# 780-00057_rev2_Pg2_SCH_NRES_Crate_Slot_M.net
KiCad netlist of a schematic drawn in Altium Designer
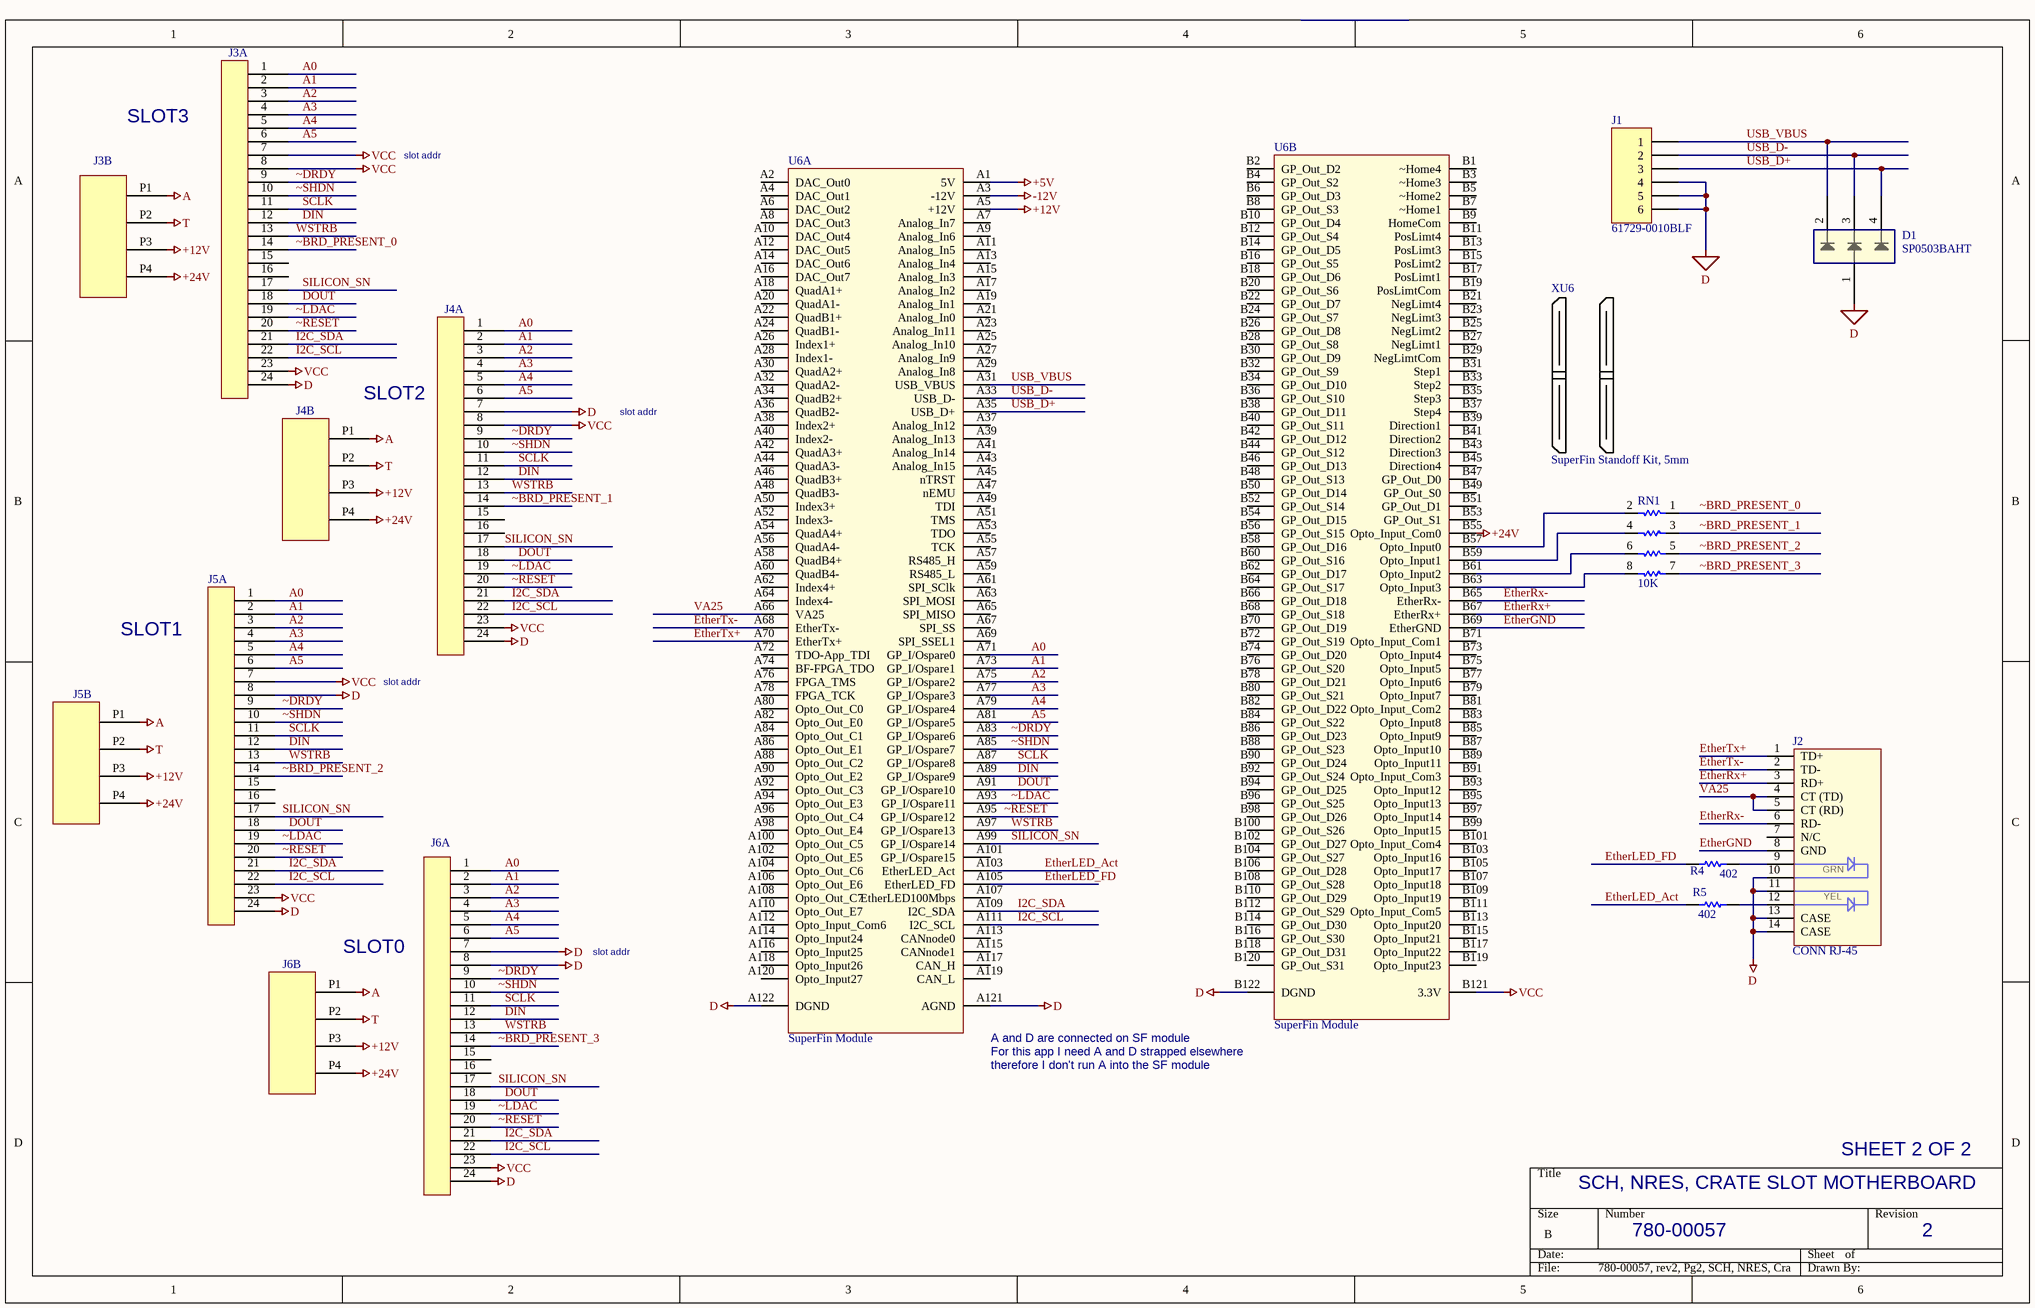
[diagram p0: 780-00057, rev2, Pg2, SCH, NRES, Crate Slot MotherBoard.SchDoc]

(export (version "E")
  (design (tool "Eeschema 10.0.6"))
  (components
    (comp (ref "D1")
      (value "SP0503BAHT")
      (footprint "SOT-143")
      (fields (field (name "MANUFACTURER") "LITTLEFUSE"))
      (libsource (lib "DJAHNG_Library_1") (part "3-Zener"))
    )
    (comp (ref "J1")
      (value "61729-0010BLF")
      (footprint "USB Vertical PCB")
      (description "Header, 6-Pin")
      (fields (field (name "MANUFACTURER") "FCI"))
      (libsource (lib "Miscellaneous Connectors") (part "Header 6"))
    )
    (comp (ref "J2")
      (value "CONN RJ-45")
      (footprint "RJ-45 w/magnetics")
      (description "Right Angle, Standard Profile, RJ45-Keyed, Flange Mount PCB Jack")
      (libsource (lib "Richs Schematic Components") (part "CONN RJ-45 with Magnetics"))
    )
    (comp (ref "J3")
      (value "Molex 46114 backplane connector, 24 signal, 4 pwr")
      (footprint "MOLEX 46114 SERIES")
      (libsource (lib "Richs Schematic Components") (part "Molex 46114 backplane connector, 24 signal, 4 pwr"))
    )
    (comp (ref "J4")
      (value "Molex 46114 backplane connector, 24 signal, 4 pwr")
      (footprint "MOLEX 46114 SERIES")
      (libsource (lib "Richs Schematic Components") (part "Molex 46114 backplane connector, 24 signal, 4 pwr"))
    )
    (comp (ref "J5")
      (value "Molex 46114 backplane connector, 24 signal, 4 pwr")
      (footprint "MOLEX 46114 SERIES")
      (libsource (lib "Richs Schematic Components") (part "Molex 46114 backplane connector, 24 signal, 4 pwr"))
    )
    (comp (ref "J6")
      (value "Molex 46114 backplane connector, 24 signal, 4 pwr")
      (footprint "MOLEX 46114 SERIES")
      (libsource (lib "Richs Schematic Components") (part "Molex 46114 backplane connector, 24 signal, 4 pwr"))
    )
    (comp (ref "R4")
      (value "402")
      (footprint "SMD_0805")
      (description "Resistor 0805")
      (fields (field (name "MANUFACTURER") "Vishay/Dale") (field (name "Comment") "Res 0805"))
      (libsource (lib "Richs Schematic Components") (part "Res SMD"))
    )
    (comp (ref "R5")
      (value "402")
      (footprint "SMD_0805")
      (description "Resistor 0805")
      (fields (field (name "MANUFACTURER") "Vishay/Dale") (field (name "Comment") "Res 0805"))
      (libsource (lib "Richs Schematic Components") (part "Res SMD"))
    )
    (comp (ref "RN1")
      (value "10K")
      (footprint "RES ARRAY 0603 x 4")
      (description "Resistor Array 4 Isolated")
      (fields (field (name "MANUFACTURER") "PANASONIC - ECG") (field (name "Comment") "RES ARRAY  x4 10K"))
      (libsource (lib "Richs Schematic Components") (part "RES ARRAY  x4 10K"))
    )
    (comp (ref "U6")
      (value "SuperFin Module")
      (footprint "SuperFin Footprint")
      (libsource (lib "Richs Schematic Components") (part "SuperFin Module"))
    )
    (comp (ref "XU6")
      (value "SuperFin Standoff Kit, 5mm")
      (libsource (lib "Richs Schematic Components") (part "SuperFin Standoff Kit, 5mm"))
    )
  )
  (nets
    (net (code "1") (name "+5V") (class "Default")
      (node (ref "U6") (pin "A1") (pinfunction "5V_A1") (pintype "passive"))
    )
    (net (code "2") (name "+12V") (class "Default")
      (node (ref "J3") (pin "P3") (pinfunction "S27_P3") (pintype "passive"))
      (node (ref "J4") (pin "P3") (pinfunction "S27_P3") (pintype "passive"))
      (node (ref "J5") (pin "P3") (pinfunction "S27_P3") (pintype "passive"))
      (node (ref "J6") (pin "P3") (pinfunction "S27_P3") (pintype "passive"))
      (node (ref "U6") (pin "A5") (pinfunction "+12V_A5") (pintype "passive"))
    )
    (net (code "3") (name "+24V") (class "Default")
      (node (ref "J3") (pin "P4") (pinfunction "S28_P4") (pintype "passive"))
      (node (ref "J4") (pin "P4") (pinfunction "S28_P4") (pintype "passive"))
      (node (ref "J5") (pin "P4") (pinfunction "S28_P4") (pintype "passive"))
      (node (ref "J6") (pin "P4") (pinfunction "S28_P4") (pintype "passive"))
      (node (ref "U6") (pin "B55") (pinfunction "Opto_Input_Com0_B55") (pintype "passive"))
    )
    (net (code "4") (name "-12V") (class "Default")
      (node (ref "U6") (pin "A3") (pinfunction "-12V_A3") (pintype "passive"))
    )
    (net (code "5") (name "/A0") (class "Default")
      (node (ref "J3") (pin "1") (pintype "passive"))
      (node (ref "J4") (pin "1") (pintype "passive"))
      (node (ref "J5") (pin "1") (pintype "passive"))
      (node (ref "J6") (pin "1") (pintype "passive"))
      (node (ref "U6") (pin "A71") (pinfunction "GP_I/Ospare0_A71") (pintype "passive"))
    )
    (net (code "6") (name "/A1") (class "Default")
      (node (ref "J3") (pin "2") (pintype "passive"))
      (node (ref "J4") (pin "2") (pintype "passive"))
      (node (ref "J5") (pin "2") (pintype "passive"))
      (node (ref "J6") (pin "2") (pintype "passive"))
      (node (ref "U6") (pin "A73") (pinfunction "GP_I/Ospare1_A73") (pintype "passive"))
    )
    (net (code "7") (name "/A2") (class "Default")
      (node (ref "J3") (pin "3") (pintype "passive"))
      (node (ref "J4") (pin "3") (pintype "passive"))
      (node (ref "J5") (pin "3") (pintype "passive"))
      (node (ref "J6") (pin "3") (pintype "passive"))
      (node (ref "U6") (pin "A75") (pinfunction "GP_I/Ospare2_A75") (pintype "passive"))
    )
    (net (code "8") (name "/A3") (class "Default")
      (node (ref "J3") (pin "4") (pintype "passive"))
      (node (ref "J4") (pin "4") (pintype "passive"))
      (node (ref "J5") (pin "4") (pintype "passive"))
      (node (ref "J6") (pin "4") (pintype "passive"))
      (node (ref "U6") (pin "A77") (pinfunction "GP_I/Ospare3_A77") (pintype "passive"))
    )
    (net (code "9") (name "/A4") (class "Default")
      (node (ref "J3") (pin "5") (pintype "passive"))
      (node (ref "J4") (pin "5") (pintype "passive"))
      (node (ref "J5") (pin "5") (pintype "passive"))
      (node (ref "J6") (pin "5") (pintype "passive"))
      (node (ref "U6") (pin "A79") (pinfunction "GP_I/Ospare4_A79") (pintype "passive"))
    )
    (net (code "10") (name "/A5") (class "Default")
      (node (ref "J3") (pin "6") (pintype "passive"))
      (node (ref "J4") (pin "6") (pintype "passive"))
      (node (ref "J5") (pin "6") (pintype "passive"))
      (node (ref "J6") (pin "6") (pintype "passive"))
      (node (ref "U6") (pin "A81") (pinfunction "GP_I/Ospare5_A81") (pintype "passive"))
    )
    (net (code "11") (name "/DIN") (class "Default")
      (node (ref "J3") (pin "12") (pintype "passive"))
      (node (ref "J4") (pin "12") (pintype "passive"))
      (node (ref "J5") (pin "12") (pintype "passive"))
      (node (ref "J6") (pin "12") (pintype "passive"))
      (node (ref "U6") (pin "A89") (pinfunction "GP_I/Ospare9_A89") (pintype "passive"))
    )
    (net (code "12") (name "/DOUT") (class "Default")
      (node (ref "J3") (pin "18") (pintype "passive"))
      (node (ref "J4") (pin "18") (pintype "passive"))
      (node (ref "J5") (pin "18") (pintype "passive"))
      (node (ref "J6") (pin "18") (pintype "passive"))
      (node (ref "U6") (pin "A91") (pinfunction "GP_I/Ospare10_A91") (pintype "passive"))
    )
    (net (code "13") (name "/EtherGND") (class "Default")
      (node (ref "J2") (pin "8") (pinfunction "GND_8") (pintype "passive"))
      (node (ref "U6") (pin "B69") (pinfunction "EtherGND_B69") (pintype "passive"))
    )
    (net (code "14") (name "/EtherLED_Act") (class "Default")
      (node (ref "R5") (pin "1") (pinfunction "1_1") (pintype "passive"))
      (node (ref "U6") (pin "A103") (pinfunction "EtherLED_Act_A103") (pintype "passive"))
    )
    (net (code "15") (name "/EtherLED_FD") (class "Default")
      (node (ref "R4") (pin "1") (pinfunction "1_1") (pintype "passive"))
      (node (ref "U6") (pin "A105") (pinfunction "EtherLED_FD_A105") (pintype "passive"))
    )
    (net (code "16") (name "/EtherRx+") (class "Default")
      (node (ref "J2") (pin "3") (pinfunction "RD+_3") (pintype "passive"))
      (node (ref "U6") (pin "B67") (pinfunction "EtherRx+_B67") (pintype "passive"))
    )
    (net (code "17") (name "/EtherRx-") (class "Default")
      (node (ref "J2") (pin "6") (pinfunction "RD-_6") (pintype "passive"))
      (node (ref "U6") (pin "B65") (pinfunction "EtherRx-_B65") (pintype "passive"))
    )
    (net (code "18") (name "/EtherTx+") (class "Default")
      (node (ref "J2") (pin "1") (pinfunction "TD+_1") (pintype "passive"))
      (node (ref "U6") (pin "A70") (pinfunction "EtherTx+_A70") (pintype "passive"))
    )
    (net (code "19") (name "/EtherTx-") (class "Default")
      (node (ref "J2") (pin "2") (pinfunction "TD-_2") (pintype "passive"))
      (node (ref "U6") (pin "A68") (pinfunction "EtherTx-_A68") (pintype "passive"))
    )
    (net (code "20") (name "/I2C_SCL") (class "Default")
      (node (ref "J3") (pin "22") (pintype "passive"))
      (node (ref "J4") (pin "22") (pintype "passive"))
      (node (ref "J5") (pin "22") (pintype "passive"))
      (node (ref "J6") (pin "22") (pintype "passive"))
      (node (ref "U6") (pin "A111") (pinfunction "I2C_SCL_A111") (pintype "passive"))
    )
    (net (code "21") (name "/I2C_SDA") (class "Default")
      (node (ref "J3") (pin "21") (pintype "passive"))
      (node (ref "J4") (pin "21") (pintype "passive"))
      (node (ref "J5") (pin "21") (pintype "passive"))
      (node (ref "J6") (pin "21") (pintype "passive"))
      (node (ref "U6") (pin "A109") (pinfunction "I2C_SDA_A109") (pintype "passive"))
    )
    (net (code "22") (name "/SCLK") (class "Default")
      (node (ref "J3") (pin "11") (pintype "passive"))
      (node (ref "J4") (pin "11") (pintype "passive"))
      (node (ref "J5") (pin "11") (pintype "passive"))
      (node (ref "J6") (pin "11") (pintype "passive"))
      (node (ref "U6") (pin "A87") (pinfunction "GP_I/Ospare8_A87") (pintype "passive"))
    )
    (net (code "23") (name "/SILICON_SN") (class "Default")
      (node (ref "J3") (pin "17") (pintype "passive"))
      (node (ref "J4") (pin "17") (pintype "passive"))
      (node (ref "J5") (pin "17") (pintype "passive"))
      (node (ref "J6") (pin "17") (pintype "passive"))
      (node (ref "U6") (pin "A99") (pinfunction "GP_I/Ospare14_A99") (pintype "passive"))
    )
    (net (code "24") (name "/USB_D+") (class "Default")
      (node (ref "D1") (pin "4") (pinfunction "K3_4") (pintype "passive"))
      (node (ref "J1") (pin "3") (pinfunction "3_3") (pintype "passive"))
      (node (ref "U6") (pin "A35") (pinfunction "USB_D+_A35") (pintype "passive"))
    )
    (net (code "25") (name "/USB_D-") (class "Default")
      (node (ref "D1") (pin "3") (pinfunction "K2_3") (pintype "passive"))
      (node (ref "J1") (pin "2") (pinfunction "2_2") (pintype "passive"))
      (node (ref "U6") (pin "A33") (pinfunction "USB_D-_A33") (pintype "passive"))
    )
    (net (code "26") (name "/USB_VBUS") (class "Default")
      (node (ref "D1") (pin "2") (pinfunction "K1_2") (pintype "passive"))
      (node (ref "J1") (pin "1") (pinfunction "1_1") (pintype "passive"))
      (node (ref "U6") (pin "A31") (pinfunction "USB_VBUS_A31") (pintype "passive"))
    )
    (net (code "27") (name "/VA25") (class "Default")
      (node (ref "J2") (pin "4") (pinfunction "CT_(TD)_4") (pintype "passive"))
      (node (ref "J2") (pin "5") (pinfunction "CT_(RD)_5") (pintype "passive"))
      (node (ref "U6") (pin "A66") (pinfunction "VA25_A66") (pintype "passive"))
    )
    (net (code "28") (name "/WSTRB") (class "Default")
      (node (ref "J3") (pin "13") (pintype "passive"))
      (node (ref "J4") (pin "13") (pintype "passive"))
      (node (ref "J5") (pin "13") (pintype "passive"))
      (node (ref "J6") (pin "13") (pintype "passive"))
      (node (ref "U6") (pin "A97") (pinfunction "GP_I/Ospare13_A97") (pintype "passive"))
    )
    (net (code "29") (name "/~BRD_PRESENT_0") (class "Default")
      (node (ref "J3") (pin "14") (pintype "passive"))
      (node (ref "RN1") (pin "1") (pinfunction "1_1") (pintype "passive"))
    )
    (net (code "30") (name "/~BRD_PRESENT_1") (class "Default")
      (node (ref "J4") (pin "14") (pintype "passive"))
      (node (ref "RN1") (pin "3") (pinfunction "3_3") (pintype "passive"))
    )
    (net (code "31") (name "/~BRD_PRESENT_2") (class "Default")
      (node (ref "J5") (pin "14") (pintype "passive"))
      (node (ref "RN1") (pin "5") (pinfunction "5_5") (pintype "passive"))
    )
    (net (code "32") (name "/~BRD_PRESENT_3") (class "Default")
      (node (ref "J6") (pin "14") (pintype "passive"))
      (node (ref "RN1") (pin "7") (pinfunction "1_7") (pintype "passive"))
    )
    (net (code "33") (name "/~DRDY") (class "Default")
      (node (ref "J3") (pin "9") (pintype "passive"))
      (node (ref "J4") (pin "9") (pintype "passive"))
      (node (ref "J5") (pin "9") (pintype "passive"))
      (node (ref "J6") (pin "9") (pintype "passive"))
      (node (ref "U6") (pin "A83") (pinfunction "GP_I/Ospare6_A83") (pintype "passive"))
    )
    (net (code "34") (name "/~LDAC") (class "Default")
      (node (ref "J3") (pin "19") (pintype "passive"))
      (node (ref "J4") (pin "19") (pintype "passive"))
      (node (ref "J5") (pin "19") (pintype "passive"))
      (node (ref "J6") (pin "19") (pintype "passive"))
      (node (ref "U6") (pin "A93") (pinfunction "GP_I/Ospare11_A93") (pintype "passive"))
    )
    (net (code "35") (name "/~RESET") (class "Default")
      (node (ref "J3") (pin "20") (pintype "passive"))
      (node (ref "J4") (pin "20") (pintype "passive"))
      (node (ref "J5") (pin "20") (pintype "passive"))
      (node (ref "J6") (pin "20") (pintype "passive"))
      (node (ref "U6") (pin "A95") (pinfunction "GP_I/Ospare12_A95") (pintype "passive"))
    )
    (net (code "36") (name "/~SHDN") (class "Default")
      (node (ref "J3") (pin "10") (pintype "passive"))
      (node (ref "J4") (pin "10") (pintype "passive"))
      (node (ref "J5") (pin "10") (pintype "passive"))
      (node (ref "J6") (pin "10") (pintype "passive"))
      (node (ref "U6") (pin "A85") (pinfunction "GP_I/Ospare7_A85") (pintype "passive"))
    )
    (net (code "37") (name "A") (class "Default")
      (node (ref "J3") (pin "P1") (pinfunction "S25_P1") (pintype "passive"))
      (node (ref "J4") (pin "P1") (pinfunction "S25_P1") (pintype "passive"))
      (node (ref "J5") (pin "P1") (pinfunction "S25_P1") (pintype "passive"))
      (node (ref "J6") (pin "P1") (pinfunction "S25_P1") (pintype "passive"))
    )
    (net (code "38") (name "D") (class "Default")
      (node (ref "D1") (pin "1") (pinfunction "A_1") (pintype "passive"))
      (node (ref "J1") (pin "4") (pinfunction "4_4") (pintype "passive"))
      (node (ref "J1") (pin "5") (pinfunction "5_5") (pintype "passive"))
      (node (ref "J1") (pin "6") (pinfunction "6_6") (pintype "passive"))
      (node (ref "J2") (pin "10") (pinfunction "GRN-Cathode_10") (pintype "passive"))
      (node (ref "J2") (pin "11") (pinfunction "YEL-Cathode_11") (pintype "passive"))
      (node (ref "J2") (pin "13") (pinfunction "CASE_13") (pintype "passive"))
      (node (ref "J2") (pin "14") (pinfunction "CASE_14") (pintype "passive"))
      (node (ref "J3") (pin "24") (pintype "passive"))
      (node (ref "J4") (pin "24") (pintype "passive"))
      (node (ref "J4") (pin "7") (pintype "passive"))
      (node (ref "J5") (pin "24") (pintype "passive"))
      (node (ref "J5") (pin "8") (pintype "passive"))
      (node (ref "J6") (pin "24") (pintype "passive"))
      (node (ref "J6") (pin "7") (pintype "passive"))
      (node (ref "J6") (pin "8") (pintype "passive"))
      (node (ref "U6") (pin "A121") (pinfunction "AGND_A121") (pintype "passive"))
      (node (ref "U6") (pin "A122") (pinfunction "DGND_A122") (pintype "passive"))
      (node (ref "U6") (pin "B122") (pinfunction "DGND_B122") (pintype "passive"))
    )
    (net (code "39") (name "Net-(J2-GRN-Anode)") (class "Default")
      (node (ref "J2") (pin "9") (pinfunction "GRN-Anode_9") (pintype "passive"))
      (node (ref "R4") (pin "2") (pinfunction "2_2") (pintype "passive"))
    )
    (net (code "40") (name "Net-(J2-YEL-Anode)") (class "Default")
      (node (ref "J2") (pin "12") (pinfunction "YEL-Anode_12") (pintype "passive"))
      (node (ref "R5") (pin "2") (pinfunction "2_2") (pintype "passive"))
    )
    (net (code "41") (name "Net-(U6B-Opto_Input0)") (class "Default")
      (node (ref "RN1") (pin "2") (pinfunction "2_2") (pintype "passive"))
      (node (ref "U6") (pin "B57") (pinfunction "Opto_Input0_B57") (pintype "passive"))
    )
    (net (code "42") (name "Net-(U6B-Opto_Input1)") (class "Default")
      (node (ref "RN1") (pin "4") (pinfunction "4_4") (pintype "passive"))
      (node (ref "U6") (pin "B59") (pinfunction "Opto_Input1_B59") (pintype "passive"))
    )
    (net (code "43") (name "Net-(U6B-Opto_Input2)") (class "Default")
      (node (ref "RN1") (pin "6") (pinfunction "6_6") (pintype "passive"))
      (node (ref "U6") (pin "B61") (pinfunction "Opto_Input2_B61") (pintype "passive"))
    )
    (net (code "44") (name "Net-(U6B-Opto_Input3)") (class "Default")
      (node (ref "RN1") (pin "8") (pinfunction "8_8") (pintype "passive"))
      (node (ref "U6") (pin "B63") (pinfunction "Opto_Input3_B63") (pintype "passive"))
    )
    (net (code "45") (name "T") (class "Default")
      (node (ref "J3") (pin "P2") (pinfunction "S26_P2") (pintype "passive"))
      (node (ref "J4") (pin "P2") (pinfunction "S26_P2") (pintype "passive"))
      (node (ref "J5") (pin "P2") (pinfunction "S26_P2") (pintype "passive"))
      (node (ref "J6") (pin "P2") (pinfunction "S26_P2") (pintype "passive"))
    )
    (net (code "46") (name "VCC") (class "Default")
      (node (ref "J3") (pin "23") (pintype "passive"))
      (node (ref "J3") (pin "7") (pintype "passive"))
      (node (ref "J3") (pin "8") (pintype "passive"))
      (node (ref "J4") (pin "23") (pintype "passive"))
      (node (ref "J4") (pin "8") (pintype "passive"))
      (node (ref "J5") (pin "23") (pintype "passive"))
      (node (ref "J5") (pin "7") (pintype "passive"))
      (node (ref "J6") (pin "23") (pintype "passive"))
      (node (ref "U6") (pin "B121") (pinfunction "3.3V_B121") (pintype "passive"))
    )
    (net (code "47") (name "unconnected-(J2-N{slash}C-Pad7)") (class "Default")
      (node (ref "J2") (pin "7") (pinfunction "N/C_7") (pintype "passive"))
    )
    (net (code "48") (name "unconnected-(J3-Pad15)") (class "Default")
      (node (ref "J3") (pin "15") (pintype "passive"))
    )
    (net (code "49") (name "unconnected-(J3-Pad16)") (class "Default")
      (node (ref "J3") (pin "16") (pintype "passive"))
    )
    (net (code "50") (name "unconnected-(J4-Pad15)") (class "Default")
      (node (ref "J4") (pin "15") (pintype "passive"))
    )
    (net (code "51") (name "unconnected-(J4-Pad16)") (class "Default")
      (node (ref "J4") (pin "16") (pintype "passive"))
    )
    (net (code "52") (name "unconnected-(J5-Pad15)") (class "Default")
      (node (ref "J5") (pin "15") (pintype "passive"))
    )
    (net (code "53") (name "unconnected-(J5-Pad16)") (class "Default")
      (node (ref "J5") (pin "16") (pintype "passive"))
    )
    (net (code "54") (name "unconnected-(J6-Pad15)") (class "Default")
      (node (ref "J6") (pin "15") (pintype "passive"))
    )
    (net (code "55") (name "unconnected-(J6-Pad16)") (class "Default")
      (node (ref "J6") (pin "16") (pintype "passive"))
    )
    (net (code "56") (name "unconnected-(U6A-Analog_In0-PadA21)") (class "Default")
      (node (ref "U6") (pin "A21") (pinfunction "Analog_In0_A21") (pintype "passive"))
    )
    (net (code "57") (name "unconnected-(U6A-Analog_In1-PadA19)") (class "Default")
      (node (ref "U6") (pin "A19") (pinfunction "Analog_In1_A19") (pintype "passive"))
    )
    (net (code "58") (name "unconnected-(U6A-Analog_In2-PadA17)") (class "Default")
      (node (ref "U6") (pin "A17") (pinfunction "Analog_In2_A17") (pintype "passive"))
    )
    (net (code "59") (name "unconnected-(U6A-Analog_In3-PadA15)") (class "Default")
      (node (ref "U6") (pin "A15") (pinfunction "Analog_In3_A15") (pintype "passive"))
    )
    (net (code "60") (name "unconnected-(U6A-Analog_In4-PadA13)") (class "Default")
      (node (ref "U6") (pin "A13") (pinfunction "Analog_In4_A13") (pintype "passive"))
    )
    (net (code "61") (name "unconnected-(U6A-Analog_In5-PadA11)") (class "Default")
      (node (ref "U6") (pin "A11") (pinfunction "Analog_In5_A11") (pintype "passive"))
    )
    (net (code "62") (name "unconnected-(U6A-Analog_In6-PadA9)") (class "Default")
      (node (ref "U6") (pin "A9") (pinfunction "Analog_In6_A9") (pintype "passive"))
    )
    (net (code "63") (name "unconnected-(U6A-Analog_In7-PadA7)") (class "Default")
      (node (ref "U6") (pin "A7") (pinfunction "Analog_In7_A7") (pintype "passive"))
    )
    (net (code "64") (name "unconnected-(U6A-Analog_In8-PadA29)") (class "Default")
      (node (ref "U6") (pin "A29") (pinfunction "Analog_In8_A29") (pintype "passive"))
    )
    (net (code "65") (name "unconnected-(U6A-Analog_In9-PadA27)") (class "Default")
      (node (ref "U6") (pin "A27") (pinfunction "Analog_In9_A27") (pintype "passive"))
    )
    (net (code "66") (name "unconnected-(U6A-Analog_In10-PadA25)") (class "Default")
      (node (ref "U6") (pin "A25") (pinfunction "Analog_In10_A25") (pintype "passive"))
    )
    (net (code "67") (name "unconnected-(U6A-Analog_In11-PadA23)") (class "Default")
      (node (ref "U6") (pin "A23") (pinfunction "Analog_In11_A23") (pintype "passive"))
    )
    (net (code "68") (name "unconnected-(U6A-Analog_In12-PadA37)") (class "Default")
      (node (ref "U6") (pin "A37") (pinfunction "Analog_In12_A37") (pintype "passive"))
    )
    (net (code "69") (name "unconnected-(U6A-Analog_In13-PadA39)") (class "Default")
      (node (ref "U6") (pin "A39") (pinfunction "Analog_In13_A39") (pintype "passive"))
    )
    (net (code "70") (name "unconnected-(U6A-Analog_In14-PadA41)") (class "Default")
      (node (ref "U6") (pin "A41") (pinfunction "Analog_In14_A41") (pintype "passive"))
    )
    (net (code "71") (name "unconnected-(U6A-Analog_In15-PadA43)") (class "Default")
      (node (ref "U6") (pin "A43") (pinfunction "Analog_In15_A43") (pintype "passive"))
    )
    (net (code "72") (name "unconnected-(U6A-BF-FPGA_TDO-PadA74)") (class "Default")
      (node (ref "U6") (pin "A74") (pinfunction "BF-FPGA_TDO_A74") (pintype "passive"))
    )
    (net (code "73") (name "unconnected-(U6A-CAN_H-PadA117)") (class "Default")
      (node (ref "U6") (pin "A117") (pinfunction "CAN_H_A117") (pintype "passive"))
    )
    (net (code "74") (name "unconnected-(U6A-CAN_L-PadA119)") (class "Default")
      (node (ref "U6") (pin "A119") (pinfunction "CAN_L_A119") (pintype "passive"))
    )
    (net (code "75") (name "unconnected-(U6A-CANnode0-PadA113)") (class "Default")
      (node (ref "U6") (pin "A113") (pinfunction "CANnode0_A113") (pintype "passive"))
    )
    (net (code "76") (name "unconnected-(U6A-CANnode1-PadA115)") (class "Default")
      (node (ref "U6") (pin "A115") (pinfunction "CANnode1_A115") (pintype "passive"))
    )
    (net (code "77") (name "unconnected-(U6A-DAC_Out0-PadA2)") (class "Default")
      (node (ref "U6") (pin "A2") (pinfunction "DAC_Out0_A2") (pintype "passive"))
    )
    (net (code "78") (name "unconnected-(U6A-DAC_Out1-PadA4)") (class "Default")
      (node (ref "U6") (pin "A4") (pinfunction "DAC_Out1_A4") (pintype "passive"))
    )
    (net (code "79") (name "unconnected-(U6A-DAC_Out2-PadA6)") (class "Default")
      (node (ref "U6") (pin "A6") (pinfunction "DAC_Out2_A6") (pintype "passive"))
    )
    (net (code "80") (name "unconnected-(U6A-DAC_Out3-PadA8)") (class "Default")
      (node (ref "U6") (pin "A8") (pinfunction "DAC_Out3_A8") (pintype "passive"))
    )
    (net (code "81") (name "unconnected-(U6A-DAC_Out4-PadA10)") (class "Default")
      (node (ref "U6") (pin "A10") (pinfunction "DAC_Out4_A10") (pintype "passive"))
    )
    (net (code "82") (name "unconnected-(U6A-DAC_Out5-PadA12)") (class "Default")
      (node (ref "U6") (pin "A12") (pinfunction "DAC_Out5_A12") (pintype "passive"))
    )
    (net (code "83") (name "unconnected-(U6A-DAC_Out6-PadA14)") (class "Default")
      (node (ref "U6") (pin "A14") (pinfunction "DAC_Out6_A14") (pintype "passive"))
    )
    (net (code "84") (name "unconnected-(U6A-DAC_Out7-PadA16)") (class "Default")
      (node (ref "U6") (pin "A16") (pinfunction "DAC_Out7_A16") (pintype "passive"))
    )
    (net (code "85") (name "unconnected-(U6A-EtherLED100Mbps-PadA107)") (class "Default")
      (node (ref "U6") (pin "A107") (pinfunction "EtherLED100Mbps_A107") (pintype "passive"))
    )
    (net (code "86") (name "unconnected-(U6A-FPGA_TCK-PadA78)") (class "Default")
      (node (ref "U6") (pin "A78") (pinfunction "FPGA_TCK_A78") (pintype "passive"))
    )
    (net (code "87") (name "unconnected-(U6A-FPGA_TMS-PadA76)") (class "Default")
      (node (ref "U6") (pin "A76") (pinfunction "FPGA_TMS_A76") (pintype "passive"))
    )
    (net (code "88") (name "unconnected-(U6A-GP_I{slash}Ospare15-PadA101)") (class "Default")
      (node (ref "U6") (pin "A101") (pinfunction "GP_I/Ospare15_A101") (pintype "passive"))
    )
    (net (code "89") (name "unconnected-(U6A-Index1+-PadA26)") (class "Default")
      (node (ref "U6") (pin "A26") (pinfunction "Index1+_A26") (pintype "passive"))
    )
    (net (code "90") (name "unconnected-(U6A-Index1--PadA28)") (class "Default")
      (node (ref "U6") (pin "A28") (pinfunction "Index1-_A28") (pintype "passive"))
    )
    (net (code "91") (name "unconnected-(U6A-Index2+-PadA38)") (class "Default")
      (node (ref "U6") (pin "A38") (pinfunction "Index2+_A38") (pintype "passive"))
    )
    (net (code "92") (name "unconnected-(U6A-Index2--PadA40)") (class "Default")
      (node (ref "U6") (pin "A40") (pinfunction "Index2-_A40") (pintype "passive"))
    )
    (net (code "93") (name "unconnected-(U6A-Index3+-PadA50)") (class "Default")
      (node (ref "U6") (pin "A50") (pinfunction "Index3+_A50") (pintype "passive"))
    )
    (net (code "94") (name "unconnected-(U6A-Index3--PadA52)") (class "Default")
      (node (ref "U6") (pin "A52") (pinfunction "Index3-_A52") (pintype "passive"))
    )
    (net (code "95") (name "unconnected-(U6A-Index4+-PadA62)") (class "Default")
      (node (ref "U6") (pin "A62") (pinfunction "Index4+_A62") (pintype "passive"))
    )
    (net (code "96") (name "unconnected-(U6A-Index4--PadA64)") (class "Default")
      (node (ref "U6") (pin "A64") (pinfunction "Index4-_A64") (pintype "passive"))
    )
    (net (code "97") (name "unconnected-(U6A-Opto_Input24-PadA114)") (class "Default")
      (node (ref "U6") (pin "A114") (pinfunction "Opto_Input24_A114") (pintype "passive"))
    )
    (net (code "98") (name "unconnected-(U6A-Opto_Input25-PadA116)") (class "Default")
      (node (ref "U6") (pin "A116") (pinfunction "Opto_Input25_A116") (pintype "passive"))
    )
    (net (code "99") (name "unconnected-(U6A-Opto_Input26-PadA118)") (class "Default")
      (node (ref "U6") (pin "A118") (pinfunction "Opto_Input26_A118") (pintype "passive"))
    )
    (net (code "100") (name "unconnected-(U6A-Opto_Input27-PadA120)") (class "Default")
      (node (ref "U6") (pin "A120") (pinfunction "Opto_Input27_A120") (pintype "passive"))
    )
    (net (code "101") (name "unconnected-(U6A-Opto_Input_Com6-PadA112)") (class "Default")
      (node (ref "U6") (pin "A112") (pinfunction "Opto_Input_Com6_A112") (pintype "passive"))
    )
    (net (code "102") (name "unconnected-(U6A-Opto_Out_C0-PadA80)") (class "Default")
      (node (ref "U6") (pin "A80") (pinfunction "Opto_Out_C0_A80") (pintype "passive"))
    )
    (net (code "103") (name "unconnected-(U6A-Opto_Out_C1-PadA84)") (class "Default")
      (node (ref "U6") (pin "A84") (pinfunction "Opto_Out_C1_A84") (pintype "passive"))
    )
    (net (code "104") (name "unconnected-(U6A-Opto_Out_C2-PadA88)") (class "Default")
      (node (ref "U6") (pin "A88") (pinfunction "Opto_Out_C2_A88") (pintype "passive"))
    )
    (net (code "105") (name "unconnected-(U6A-Opto_Out_C3-PadA92)") (class "Default")
      (node (ref "U6") (pin "A92") (pinfunction "Opto_Out_C3_A92") (pintype "passive"))
    )
    (net (code "106") (name "unconnected-(U6A-Opto_Out_C4-PadA96)") (class "Default")
      (node (ref "U6") (pin "A96") (pinfunction "Opto_Out_C4_A96") (pintype "passive"))
    )
    (net (code "107") (name "unconnected-(U6A-Opto_Out_C5-PadA100)") (class "Default")
      (node (ref "U6") (pin "A100") (pinfunction "Opto_Out_C5_A100") (pintype "passive"))
    )
    (net (code "108") (name "unconnected-(U6A-Opto_Out_C6-PadA104)") (class "Default")
      (node (ref "U6") (pin "A104") (pinfunction "Opto_Out_C6_A104") (pintype "passive"))
    )
    (net (code "109") (name "unconnected-(U6A-Opto_Out_C7-PadA108)") (class "Default")
      (node (ref "U6") (pin "A108") (pinfunction "Opto_Out_C7_A108") (pintype "passive"))
    )
    (net (code "110") (name "unconnected-(U6A-Opto_Out_E0-PadA82)") (class "Default")
      (node (ref "U6") (pin "A82") (pinfunction "Opto_Out_E0_A82") (pintype "passive"))
    )
    (net (code "111") (name "unconnected-(U6A-Opto_Out_E1-PadA86)") (class "Default")
      (node (ref "U6") (pin "A86") (pinfunction "Opto_Out_E1_A86") (pintype "passive"))
    )
    (net (code "112") (name "unconnected-(U6A-Opto_Out_E2-PadA90)") (class "Default")
      (node (ref "U6") (pin "A90") (pinfunction "Opto_Out_E2_A90") (pintype "passive"))
    )
    (net (code "113") (name "unconnected-(U6A-Opto_Out_E3-PadA94)") (class "Default")
      (node (ref "U6") (pin "A94") (pinfunction "Opto_Out_E3_A94") (pintype "passive"))
    )
    (net (code "114") (name "unconnected-(U6A-Opto_Out_E4-PadA98)") (class "Default")
      (node (ref "U6") (pin "A98") (pinfunction "Opto_Out_E4_A98") (pintype "passive"))
    )
    (net (code "115") (name "unconnected-(U6A-Opto_Out_E5-PadA102)") (class "Default")
      (node (ref "U6") (pin "A102") (pinfunction "Opto_Out_E5_A102") (pintype "passive"))
    )
    (net (code "116") (name "unconnected-(U6A-Opto_Out_E6-PadA106)") (class "Default")
      (node (ref "U6") (pin "A106") (pinfunction "Opto_Out_E6_A106") (pintype "passive"))
    )
    (net (code "117") (name "unconnected-(U6A-Opto_Out_E7-PadA110)") (class "Default")
      (node (ref "U6") (pin "A110") (pinfunction "Opto_Out_E7_A110") (pintype "passive"))
    )
    (net (code "118") (name "unconnected-(U6A-QuadA1+-PadA18)") (class "Default")
      (node (ref "U6") (pin "A18") (pinfunction "QuadA1+_A18") (pintype "passive"))
    )
    (net (code "119") (name "unconnected-(U6A-QuadA1--PadA20)") (class "Default")
      (node (ref "U6") (pin "A20") (pinfunction "QuadA1-_A20") (pintype "passive"))
    )
    (net (code "120") (name "unconnected-(U6A-QuadA2+-PadA30)") (class "Default")
      (node (ref "U6") (pin "A30") (pinfunction "QuadA2+_A30") (pintype "passive"))
    )
    (net (code "121") (name "unconnected-(U6A-QuadA2--PadA32)") (class "Default")
      (node (ref "U6") (pin "A32") (pinfunction "QuadA2-_A32") (pintype "passive"))
    )
    (net (code "122") (name "unconnected-(U6A-QuadA3+-PadA42)") (class "Default")
      (node (ref "U6") (pin "A42") (pinfunction "QuadA3+_A42") (pintype "passive"))
    )
    (net (code "123") (name "unconnected-(U6A-QuadA3--PadA44)") (class "Default")
      (node (ref "U6") (pin "A44") (pinfunction "QuadA3-_A44") (pintype "passive"))
    )
    (net (code "124") (name "unconnected-(U6A-QuadA4+-PadA54)") (class "Default")
      (node (ref "U6") (pin "A54") (pinfunction "QuadA4+_A54") (pintype "passive"))
    )
    (net (code "125") (name "unconnected-(U6A-QuadA4--PadA56)") (class "Default")
      (node (ref "U6") (pin "A56") (pinfunction "QuadA4-_A56") (pintype "passive"))
    )
    (net (code "126") (name "unconnected-(U6A-QuadB1+-PadA22)") (class "Default")
      (node (ref "U6") (pin "A22") (pinfunction "QuadB1+_A22") (pintype "passive"))
    )
    (net (code "127") (name "unconnected-(U6A-QuadB1--PadA24)") (class "Default")
      (node (ref "U6") (pin "A24") (pinfunction "QuadB1-_A24") (pintype "passive"))
    )
    (net (code "128") (name "unconnected-(U6A-QuadB2+-PadA34)") (class "Default")
      (node (ref "U6") (pin "A34") (pinfunction "QuadB2+_A34") (pintype "passive"))
    )
    (net (code "129") (name "unconnected-(U6A-QuadB2--PadA36)") (class "Default")
      (node (ref "U6") (pin "A36") (pinfunction "QuadB2-_A36") (pintype "passive"))
    )
    (net (code "130") (name "unconnected-(U6A-QuadB3+-PadA46)") (class "Default")
      (node (ref "U6") (pin "A46") (pinfunction "QuadB3+_A46") (pintype "passive"))
    )
    (net (code "131") (name "unconnected-(U6A-QuadB3--PadA48)") (class "Default")
      (node (ref "U6") (pin "A48") (pinfunction "QuadB3-_A48") (pintype "passive"))
    )
    (net (code "132") (name "unconnected-(U6A-QuadB4+-PadA58)") (class "Default")
      (node (ref "U6") (pin "A58") (pinfunction "QuadB4+_A58") (pintype "passive"))
    )
    (net (code "133") (name "unconnected-(U6A-QuadB4--PadA60)") (class "Default")
      (node (ref "U6") (pin "A60") (pinfunction "QuadB4-_A60") (pintype "passive"))
    )
    (net (code "134") (name "unconnected-(U6A-RS485_H-PadA57)") (class "Default")
      (node (ref "U6") (pin "A57") (pinfunction "RS485_H_A57") (pintype "passive"))
    )
    (net (code "135") (name "unconnected-(U6A-RS485_L-PadA59)") (class "Default")
      (node (ref "U6") (pin "A59") (pinfunction "RS485_L_A59") (pintype "passive"))
    )
    (net (code "136") (name "unconnected-(U6A-SPI_MISO-PadA65)") (class "Default")
      (node (ref "U6") (pin "A65") (pinfunction "SPI_MISO_A65") (pintype "passive"))
    )
    (net (code "137") (name "unconnected-(U6A-SPI_MOSI-PadA63)") (class "Default")
      (node (ref "U6") (pin "A63") (pinfunction "SPI_MOSI_A63") (pintype "passive"))
    )
    (net (code "138") (name "unconnected-(U6A-SPI_SClk-PadA61)") (class "Default")
      (node (ref "U6") (pin "A61") (pinfunction "SPI_SClk_A61") (pintype "passive"))
    )
    (net (code "139") (name "unconnected-(U6A-SPI_SS-PadA67)") (class "Default")
      (node (ref "U6") (pin "A67") (pinfunction "SPI_SS_A67") (pintype "passive"))
    )
    (net (code "140") (name "unconnected-(U6A-SPI_SSEL1-PadA69)") (class "Default")
      (node (ref "U6") (pin "A69") (pinfunction "SPI_SSEL1_A69") (pintype "passive"))
    )
    (net (code "141") (name "unconnected-(U6A-TCK-PadA55)") (class "Default")
      (node (ref "U6") (pin "A55") (pinfunction "TCK_A55") (pintype "passive"))
    )
    (net (code "142") (name "unconnected-(U6A-TDI-PadA49)") (class "Default")
      (node (ref "U6") (pin "A49") (pinfunction "TDI_A49") (pintype "passive"))
    )
    (net (code "143") (name "unconnected-(U6A-TDO-App_TDI-PadA72)") (class "Default")
      (node (ref "U6") (pin "A72") (pinfunction "TDO-App_TDI_A72") (pintype "passive"))
    )
    (net (code "144") (name "unconnected-(U6A-TDO-PadA53)") (class "Default")
      (node (ref "U6") (pin "A53") (pinfunction "TDO_A53") (pintype "passive"))
    )
    (net (code "145") (name "unconnected-(U6A-TMS-PadA51)") (class "Default")
      (node (ref "U6") (pin "A51") (pinfunction "TMS_A51") (pintype "passive"))
    )
    (net (code "146") (name "unconnected-(U6A-nEMU-PadA47)") (class "Default")
      (node (ref "U6") (pin "A47") (pinfunction "nEMU_A47") (pintype "passive"))
    )
    (net (code "147") (name "unconnected-(U6A-nTRST-PadA45)") (class "Default")
      (node (ref "U6") (pin "A45") (pinfunction "nTRST_A45") (pintype "passive"))
    )
    (net (code "148") (name "unconnected-(U6B-Direction1-PadB39)") (class "Default")
      (node (ref "U6") (pin "B39") (pinfunction "Direction1_B39") (pintype "passive"))
    )
    (net (code "149") (name "unconnected-(U6B-Direction2-PadB41)") (class "Default")
      (node (ref "U6") (pin "B41") (pinfunction "Direction2_B41") (pintype "passive"))
    )
    (net (code "150") (name "unconnected-(U6B-Direction3-PadB43)") (class "Default")
      (node (ref "U6") (pin "B43") (pinfunction "Direction3_B43") (pintype "passive"))
    )
    (net (code "151") (name "unconnected-(U6B-Direction4-PadB45)") (class "Default")
      (node (ref "U6") (pin "B45") (pinfunction "Direction4_B45") (pintype "passive"))
    )
    (net (code "152") (name "unconnected-(U6B-GP_Out_D0-PadB47)") (class "Default")
      (node (ref "U6") (pin "B47") (pinfunction "GP_Out_D0_B47") (pintype "passive"))
    )
    (net (code "153") (name "unconnected-(U6B-GP_Out_D1-PadB51)") (class "Default")
      (node (ref "U6") (pin "B51") (pinfunction "GP_Out_D1_B51") (pintype "passive"))
    )
    (net (code "154") (name "unconnected-(U6B-GP_Out_D2-PadB2)") (class "Default")
      (node (ref "U6") (pin "B2") (pinfunction "GP_Out_D2_B2") (pintype "passive"))
    )
    (net (code "155") (name "unconnected-(U6B-GP_Out_D3-PadB6)") (class "Default")
      (node (ref "U6") (pin "B6") (pinfunction "GP_Out_D3_B6") (pintype "passive"))
    )
    (net (code "156") (name "unconnected-(U6B-GP_Out_D4-PadB10)") (class "Default")
      (node (ref "U6") (pin "B10") (pinfunction "GP_Out_D4_B10") (pintype "passive"))
    )
    (net (code "157") (name "unconnected-(U6B-GP_Out_D5-PadB14)") (class "Default")
      (node (ref "U6") (pin "B14") (pinfunction "GP_Out_D5_B14") (pintype "passive"))
    )
    (net (code "158") (name "unconnected-(U6B-GP_Out_D6-PadB18)") (class "Default")
      (node (ref "U6") (pin "B18") (pinfunction "GP_Out_D6_B18") (pintype "passive"))
    )
    (net (code "159") (name "unconnected-(U6B-GP_Out_D7-PadB22)") (class "Default")
      (node (ref "U6") (pin "B22") (pinfunction "GP_Out_D7_B22") (pintype "passive"))
    )
    (net (code "160") (name "unconnected-(U6B-GP_Out_D8-PadB26)") (class "Default")
      (node (ref "U6") (pin "B26") (pinfunction "GP_Out_D8_B26") (pintype "passive"))
    )
    (net (code "161") (name "unconnected-(U6B-GP_Out_D9-PadB30)") (class "Default")
      (node (ref "U6") (pin "B30") (pinfunction "GP_Out_D9_B30") (pintype "passive"))
    )
    (net (code "162") (name "unconnected-(U6B-GP_Out_D10-PadB34)") (class "Default")
      (node (ref "U6") (pin "B34") (pinfunction "GP_Out_D10_B34") (pintype "passive"))
    )
    (net (code "163") (name "unconnected-(U6B-GP_Out_D11-PadB38)") (class "Default")
      (node (ref "U6") (pin "B38") (pinfunction "GP_Out_D11_B38") (pintype "passive"))
    )
    (net (code "164") (name "unconnected-(U6B-GP_Out_D12-PadB42)") (class "Default")
      (node (ref "U6") (pin "B42") (pinfunction "GP_Out_D12_B42") (pintype "passive"))
    )
    (net (code "165") (name "unconnected-(U6B-GP_Out_D13-PadB46)") (class "Default")
      (node (ref "U6") (pin "B46") (pinfunction "GP_Out_D13_B46") (pintype "passive"))
    )
    (net (code "166") (name "unconnected-(U6B-GP_Out_D14-PadB50)") (class "Default")
      (node (ref "U6") (pin "B50") (pinfunction "GP_Out_D14_B50") (pintype "passive"))
    )
    (net (code "167") (name "unconnected-(U6B-GP_Out_D15-PadB54)") (class "Default")
      (node (ref "U6") (pin "B54") (pinfunction "GP_Out_D15_B54") (pintype "passive"))
    )
    (net (code "168") (name "unconnected-(U6B-GP_Out_D16-PadB58)") (class "Default")
      (node (ref "U6") (pin "B58") (pinfunction "GP_Out_D16_B58") (pintype "passive"))
    )
    (net (code "169") (name "unconnected-(U6B-GP_Out_D17-PadB62)") (class "Default")
      (node (ref "U6") (pin "B62") (pinfunction "GP_Out_D17_B62") (pintype "passive"))
    )
    (net (code "170") (name "unconnected-(U6B-GP_Out_D18-PadB66)") (class "Default")
      (node (ref "U6") (pin "B66") (pinfunction "GP_Out_D18_B66") (pintype "passive"))
    )
    (net (code "171") (name "unconnected-(U6B-GP_Out_D19-PadB70)") (class "Default")
      (node (ref "U6") (pin "B70") (pinfunction "GP_Out_D19_B70") (pintype "passive"))
    )
    (net (code "172") (name "unconnected-(U6B-GP_Out_D20-PadB74)") (class "Default")
      (node (ref "U6") (pin "B74") (pinfunction "GP_Out_D20_B74") (pintype "passive"))
    )
    (net (code "173") (name "unconnected-(U6B-GP_Out_D21-PadB78)") (class "Default")
      (node (ref "U6") (pin "B78") (pinfunction "GP_Out_D21_B78") (pintype "passive"))
    )
    (net (code "174") (name "unconnected-(U6B-GP_Out_D22-PadB82)") (class "Default")
      (node (ref "U6") (pin "B82") (pinfunction "GP_Out_D22_B82") (pintype "passive"))
    )
    (net (code "175") (name "unconnected-(U6B-GP_Out_D23-PadB86)") (class "Default")
      (node (ref "U6") (pin "B86") (pinfunction "GP_Out_D23_B86") (pintype "passive"))
    )
    (net (code "176") (name "unconnected-(U6B-GP_Out_D24-PadB90)") (class "Default")
      (node (ref "U6") (pin "B90") (pinfunction "GP_Out_D24_B90") (pintype "passive"))
    )
    (net (code "177") (name "unconnected-(U6B-GP_Out_D25-PadB94)") (class "Default")
      (node (ref "U6") (pin "B94") (pinfunction "GP_Out_D25_B94") (pintype "passive"))
    )
    (net (code "178") (name "unconnected-(U6B-GP_Out_D26-PadB98)") (class "Default")
      (node (ref "U6") (pin "B98") (pinfunction "GP_Out_D26_B98") (pintype "passive"))
    )
    (net (code "179") (name "unconnected-(U6B-GP_Out_D27-PadB102)") (class "Default")
      (node (ref "U6") (pin "B102") (pinfunction "GP_Out_D27_B102") (pintype "passive"))
    )
    (net (code "180") (name "unconnected-(U6B-GP_Out_D28-PadB106)") (class "Default")
      (node (ref "U6") (pin "B106") (pinfunction "GP_Out_D28_B106") (pintype "passive"))
    )
    (net (code "181") (name "unconnected-(U6B-GP_Out_D29-PadB110)") (class "Default")
      (node (ref "U6") (pin "B110") (pinfunction "GP_Out_D29_B110") (pintype "passive"))
    )
    (net (code "182") (name "unconnected-(U6B-GP_Out_D30-PadB114)") (class "Default")
      (node (ref "U6") (pin "B114") (pinfunction "GP_Out_D30_B114") (pintype "passive"))
    )
    (net (code "183") (name "unconnected-(U6B-GP_Out_D31-PadB118)") (class "Default")
      (node (ref "U6") (pin "B118") (pinfunction "GP_Out_D31_B118") (pintype "passive"))
    )
    (net (code "184") (name "unconnected-(U6B-GP_Out_S0-PadB49)") (class "Default")
      (node (ref "U6") (pin "B49") (pinfunction "GP_Out_S0_B49") (pintype "passive"))
    )
    (net (code "185") (name "unconnected-(U6B-GP_Out_S1-PadB53)") (class "Default")
      (node (ref "U6") (pin "B53") (pinfunction "GP_Out_S1_B53") (pintype "passive"))
    )
    (net (code "186") (name "unconnected-(U6B-GP_Out_S2-PadB4)") (class "Default")
      (node (ref "U6") (pin "B4") (pinfunction "GP_Out_S2_B4") (pintype "passive"))
    )
    (net (code "187") (name "unconnected-(U6B-GP_Out_S3-PadB8)") (class "Default")
      (node (ref "U6") (pin "B8") (pinfunction "GP_Out_S3_B8") (pintype "passive"))
    )
    (net (code "188") (name "unconnected-(U6B-GP_Out_S4-PadB12)") (class "Default")
      (node (ref "U6") (pin "B12") (pinfunction "GP_Out_S4_B12") (pintype "passive"))
    )
    (net (code "189") (name "unconnected-(U6B-GP_Out_S5-PadB16)") (class "Default")
      (node (ref "U6") (pin "B16") (pinfunction "GP_Out_S5_B16") (pintype "passive"))
    )
    (net (code "190") (name "unconnected-(U6B-GP_Out_S6-PadB20)") (class "Default")
      (node (ref "U6") (pin "B20") (pinfunction "GP_Out_S6_B20") (pintype "passive"))
    )
    (net (code "191") (name "unconnected-(U6B-GP_Out_S7-PadB24)") (class "Default")
      (node (ref "U6") (pin "B24") (pinfunction "GP_Out_S7_B24") (pintype "passive"))
    )
    (net (code "192") (name "unconnected-(U6B-GP_Out_S8-PadB28)") (class "Default")
      (node (ref "U6") (pin "B28") (pinfunction "GP_Out_S8_B28") (pintype "passive"))
    )
    (net (code "193") (name "unconnected-(U6B-GP_Out_S9-PadB32)") (class "Default")
      (node (ref "U6") (pin "B32") (pinfunction "GP_Out_S9_B32") (pintype "passive"))
    )
    (net (code "194") (name "unconnected-(U6B-GP_Out_S10-PadB36)") (class "Default")
      (node (ref "U6") (pin "B36") (pinfunction "GP_Out_S10_B36") (pintype "passive"))
    )
    (net (code "195") (name "unconnected-(U6B-GP_Out_S11-PadB40)") (class "Default")
      (node (ref "U6") (pin "B40") (pinfunction "GP_Out_S11_B40") (pintype "passive"))
    )
    (net (code "196") (name "unconnected-(U6B-GP_Out_S12-PadB44)") (class "Default")
      (node (ref "U6") (pin "B44") (pinfunction "GP_Out_S12_B44") (pintype "passive"))
    )
    (net (code "197") (name "unconnected-(U6B-GP_Out_S13-PadB48)") (class "Default")
      (node (ref "U6") (pin "B48") (pinfunction "GP_Out_S13_B48") (pintype "passive"))
    )
    (net (code "198") (name "unconnected-(U6B-GP_Out_S14-PadB52)") (class "Default")
      (node (ref "U6") (pin "B52") (pinfunction "GP_Out_S14_B52") (pintype "passive"))
    )
    (net (code "199") (name "unconnected-(U6B-GP_Out_S15-PadB56)") (class "Default")
      (node (ref "U6") (pin "B56") (pinfunction "GP_Out_S15_B56") (pintype "passive"))
    )
    (net (code "200") (name "unconnected-(U6B-GP_Out_S16-PadB60)") (class "Default")
      (node (ref "U6") (pin "B60") (pinfunction "GP_Out_S16_B60") (pintype "passive"))
    )
    (net (code "201") (name "unconnected-(U6B-GP_Out_S17-PadB64)") (class "Default")
      (node (ref "U6") (pin "B64") (pinfunction "GP_Out_S17_B64") (pintype "passive"))
    )
    (net (code "202") (name "unconnected-(U6B-GP_Out_S18-PadB68)") (class "Default")
      (node (ref "U6") (pin "B68") (pinfunction "GP_Out_S18_B68") (pintype "passive"))
    )
    (net (code "203") (name "unconnected-(U6B-GP_Out_S19-PadB72)") (class "Default")
      (node (ref "U6") (pin "B72") (pinfunction "GP_Out_S19_B72") (pintype "passive"))
    )
    (net (code "204") (name "unconnected-(U6B-GP_Out_S20-PadB76)") (class "Default")
      (node (ref "U6") (pin "B76") (pinfunction "GP_Out_S20_B76") (pintype "passive"))
    )
    (net (code "205") (name "unconnected-(U6B-GP_Out_S21-PadB80)") (class "Default")
      (node (ref "U6") (pin "B80") (pinfunction "GP_Out_S21_B80") (pintype "passive"))
    )
    (net (code "206") (name "unconnected-(U6B-GP_Out_S22-PadB84)") (class "Default")
      (node (ref "U6") (pin "B84") (pinfunction "GP_Out_S22_B84") (pintype "passive"))
    )
    (net (code "207") (name "unconnected-(U6B-GP_Out_S23-PadB88)") (class "Default")
      (node (ref "U6") (pin "B88") (pinfunction "GP_Out_S23_B88") (pintype "passive"))
    )
    (net (code "208") (name "unconnected-(U6B-GP_Out_S24-PadB92)") (class "Default")
      (node (ref "U6") (pin "B92") (pinfunction "GP_Out_S24_B92") (pintype "passive"))
    )
    (net (code "209") (name "unconnected-(U6B-GP_Out_S25-PadB96)") (class "Default")
      (node (ref "U6") (pin "B96") (pinfunction "GP_Out_S25_B96") (pintype "passive"))
    )
    (net (code "210") (name "unconnected-(U6B-GP_Out_S26-PadB100)") (class "Default")
      (node (ref "U6") (pin "B100") (pinfunction "GP_Out_S26_B100") (pintype "passive"))
    )
    (net (code "211") (name "unconnected-(U6B-GP_Out_S27-PadB104)") (class "Default")
      (node (ref "U6") (pin "B104") (pinfunction "GP_Out_S27_B104") (pintype "passive"))
    )
    (net (code "212") (name "unconnected-(U6B-GP_Out_S28-PadB108)") (class "Default")
      (node (ref "U6") (pin "B108") (pinfunction "GP_Out_S28_B108") (pintype "passive"))
    )
    (net (code "213") (name "unconnected-(U6B-GP_Out_S29-PadB112)") (class "Default")
      (node (ref "U6") (pin "B112") (pinfunction "GP_Out_S29_B112") (pintype "passive"))
    )
    (net (code "214") (name "unconnected-(U6B-GP_Out_S30-PadB116)") (class "Default")
      (node (ref "U6") (pin "B116") (pinfunction "GP_Out_S30_B116") (pintype "passive"))
    )
    (net (code "215") (name "unconnected-(U6B-GP_Out_S31-PadB120)") (class "Default")
      (node (ref "U6") (pin "B120") (pinfunction "GP_Out_S31_B120") (pintype "passive"))
    )
    (net (code "216") (name "unconnected-(U6B-HomeCom-PadB9)") (class "Default")
      (node (ref "U6") (pin "B9") (pinfunction "HomeCom_B9") (pintype "passive"))
    )
    (net (code "217") (name "unconnected-(U6B-NegLimt1-PadB27)") (class "Default")
      (node (ref "U6") (pin "B27") (pinfunction "NegLimt1_B27") (pintype "passive"))
    )
    (net (code "218") (name "unconnected-(U6B-NegLimt2-PadB25)") (class "Default")
      (node (ref "U6") (pin "B25") (pinfunction "NegLimt2_B25") (pintype "passive"))
    )
    (net (code "219") (name "unconnected-(U6B-NegLimt3-PadB23)") (class "Default")
      (node (ref "U6") (pin "B23") (pinfunction "NegLimt3_B23") (pintype "passive"))
    )
    (net (code "220") (name "unconnected-(U6B-NegLimt4-PadB21)") (class "Default")
      (node (ref "U6") (pin "B21") (pinfunction "NegLimt4_B21") (pintype "passive"))
    )
    (net (code "221") (name "unconnected-(U6B-NegLimtCom-PadB29)") (class "Default")
      (node (ref "U6") (pin "B29") (pinfunction "NegLimtCom_B29") (pintype "passive"))
    )
    (net (code "222") (name "unconnected-(U6B-Opto_Input4-PadB73)") (class "Default")
      (node (ref "U6") (pin "B73") (pinfunction "Opto_Input4_B73") (pintype "passive"))
    )
    (net (code "223") (name "unconnected-(U6B-Opto_Input5-PadB75)") (class "Default")
      (node (ref "U6") (pin "B75") (pinfunction "Opto_Input5_B75") (pintype "passive"))
    )
    (net (code "224") (name "unconnected-(U6B-Opto_Input6-PadB77)") (class "Default")
      (node (ref "U6") (pin "B77") (pinfunction "Opto_Input6_B77") (pintype "passive"))
    )
    (net (code "225") (name "unconnected-(U6B-Opto_Input7-PadB79)") (class "Default")
      (node (ref "U6") (pin "B79") (pinfunction "Opto_Input7_B79") (pintype "passive"))
    )
    (net (code "226") (name "unconnected-(U6B-Opto_Input8-PadB83)") (class "Default")
      (node (ref "U6") (pin "B83") (pinfunction "Opto_Input8_B83") (pintype "passive"))
    )
    (net (code "227") (name "unconnected-(U6B-Opto_Input9-PadB85)") (class "Default")
      (node (ref "U6") (pin "B85") (pinfunction "Opto_Input9_B85") (pintype "passive"))
    )
    (net (code "228") (name "unconnected-(U6B-Opto_Input10-PadB87)") (class "Default")
      (node (ref "U6") (pin "B87") (pinfunction "Opto_Input10_B87") (pintype "passive"))
    )
    (net (code "229") (name "unconnected-(U6B-Opto_Input11-PadB89)") (class "Default")
      (node (ref "U6") (pin "B89") (pinfunction "Opto_Input11_B89") (pintype "passive"))
    )
    (net (code "230") (name "unconnected-(U6B-Opto_Input12-PadB93)") (class "Default")
      (node (ref "U6") (pin "B93") (pinfunction "Opto_Input12_B93") (pintype "passive"))
    )
    (net (code "231") (name "unconnected-(U6B-Opto_Input13-PadB95)") (class "Default")
      (node (ref "U6") (pin "B95") (pinfunction "Opto_Input13_B95") (pintype "passive"))
    )
    (net (code "232") (name "unconnected-(U6B-Opto_Input14-PadB97)") (class "Default")
      (node (ref "U6") (pin "B97") (pinfunction "Opto_Input14_B97") (pintype "passive"))
    )
    (net (code "233") (name "unconnected-(U6B-Opto_Input15-PadB99)") (class "Default")
      (node (ref "U6") (pin "B99") (pinfunction "Opto_Input15_B99") (pintype "passive"))
    )
    (net (code "234") (name "unconnected-(U6B-Opto_Input16-PadB103)") (class "Default")
      (node (ref "U6") (pin "B103") (pinfunction "Opto_Input16_B103") (pintype "passive"))
    )
    (net (code "235") (name "unconnected-(U6B-Opto_Input17-PadB105)") (class "Default")
      (node (ref "U6") (pin "B105") (pinfunction "Opto_Input17_B105") (pintype "passive"))
    )
    (net (code "236") (name "unconnected-(U6B-Opto_Input18-PadB107)") (class "Default")
      (node (ref "U6") (pin "B107") (pinfunction "Opto_Input18_B107") (pintype "passive"))
    )
    (net (code "237") (name "unconnected-(U6B-Opto_Input19-PadB109)") (class "Default")
      (node (ref "U6") (pin "B109") (pinfunction "Opto_Input19_B109") (pintype "passive"))
    )
    (net (code "238") (name "unconnected-(U6B-Opto_Input20-PadB113)") (class "Default")
      (node (ref "U6") (pin "B113") (pinfunction "Opto_Input20_B113") (pintype "passive"))
    )
    (net (code "239") (name "unconnected-(U6B-Opto_Input21-PadB115)") (class "Default")
      (node (ref "U6") (pin "B115") (pinfunction "Opto_Input21_B115") (pintype "passive"))
    )
    (net (code "240") (name "unconnected-(U6B-Opto_Input22-PadB117)") (class "Default")
      (node (ref "U6") (pin "B117") (pinfunction "Opto_Input22_B117") (pintype "passive"))
    )
    (net (code "241") (name "unconnected-(U6B-Opto_Input23-PadB119)") (class "Default")
      (node (ref "U6") (pin "B119") (pinfunction "Opto_Input23_B119") (pintype "passive"))
    )
    (net (code "242") (name "unconnected-(U6B-Opto_Input_Com1-PadB71)") (class "Default")
      (node (ref "U6") (pin "B71") (pinfunction "Opto_Input_Com1_B71") (pintype "passive"))
    )
    (net (code "243") (name "unconnected-(U6B-Opto_Input_Com2-PadB81)") (class "Default")
      (node (ref "U6") (pin "B81") (pinfunction "Opto_Input_Com2_B81") (pintype "passive"))
    )
    (net (code "244") (name "unconnected-(U6B-Opto_Input_Com3-PadB91)") (class "Default")
      (node (ref "U6") (pin "B91") (pinfunction "Opto_Input_Com3_B91") (pintype "passive"))
    )
    (net (code "245") (name "unconnected-(U6B-Opto_Input_Com4-PadB101)") (class "Default")
      (node (ref "U6") (pin "B101") (pinfunction "Opto_Input_Com4_B101") (pintype "passive"))
    )
    (net (code "246") (name "unconnected-(U6B-Opto_Input_Com5-PadB111)") (class "Default")
      (node (ref "U6") (pin "B111") (pinfunction "Opto_Input_Com5_B111") (pintype "passive"))
    )
    (net (code "247") (name "unconnected-(U6B-PosLimt1-PadB17)") (class "Default")
      (node (ref "U6") (pin "B17") (pinfunction "PosLimt1_B17") (pintype "passive"))
    )
    (net (code "248") (name "unconnected-(U6B-PosLimt2-PadB15)") (class "Default")
      (node (ref "U6") (pin "B15") (pinfunction "PosLimt2_B15") (pintype "passive"))
    )
    (net (code "249") (name "unconnected-(U6B-PosLimt3-PadB13)") (class "Default")
      (node (ref "U6") (pin "B13") (pinfunction "PosLimt3_B13") (pintype "passive"))
    )
    (net (code "250") (name "unconnected-(U6B-PosLimt4-PadB11)") (class "Default")
      (node (ref "U6") (pin "B11") (pinfunction "PosLimt4_B11") (pintype "passive"))
    )
    (net (code "251") (name "unconnected-(U6B-PosLimtCom-PadB19)") (class "Default")
      (node (ref "U6") (pin "B19") (pinfunction "PosLimtCom_B19") (pintype "passive"))
    )
    (net (code "252") (name "unconnected-(U6B-Step1-PadB31)") (class "Default")
      (node (ref "U6") (pin "B31") (pinfunction "Step1_B31") (pintype "passive"))
    )
    (net (code "253") (name "unconnected-(U6B-Step2-PadB33)") (class "Default")
      (node (ref "U6") (pin "B33") (pinfunction "Step2_B33") (pintype "passive"))
    )
    (net (code "254") (name "unconnected-(U6B-Step3-PadB35)") (class "Default")
      (node (ref "U6") (pin "B35") (pinfunction "Step3_B35") (pintype "passive"))
    )
    (net (code "255") (name "unconnected-(U6B-Step4-PadB37)") (class "Default")
      (node (ref "U6") (pin "B37") (pinfunction "Step4_B37") (pintype "passive"))
    )
    (net (code "256") (name "unconnected-(U6B-~Home1-PadB7)") (class "Default")
      (node (ref "U6") (pin "B7") (pinfunction "~Home1_B7") (pintype "passive"))
    )
    (net (code "257") (name "unconnected-(U6B-~Home2-PadB5)") (class "Default")
      (node (ref "U6") (pin "B5") (pinfunction "~Home2_B5") (pintype "passive"))
    )
    (net (code "258") (name "unconnected-(U6B-~Home3-PadB3)") (class "Default")
      (node (ref "U6") (pin "B3") (pinfunction "~Home3_B3") (pintype "passive"))
    )
    (net (code "259") (name "unconnected-(U6B-~Home4-PadB1)") (class "Default")
      (node (ref "U6") (pin "B1") (pinfunction "~Home4_B1") (pintype "passive"))
    )
  )
)
